# Bluetooth_Module_Programmer.net
KiCad netlist of a schematic drawn in Altium Designer
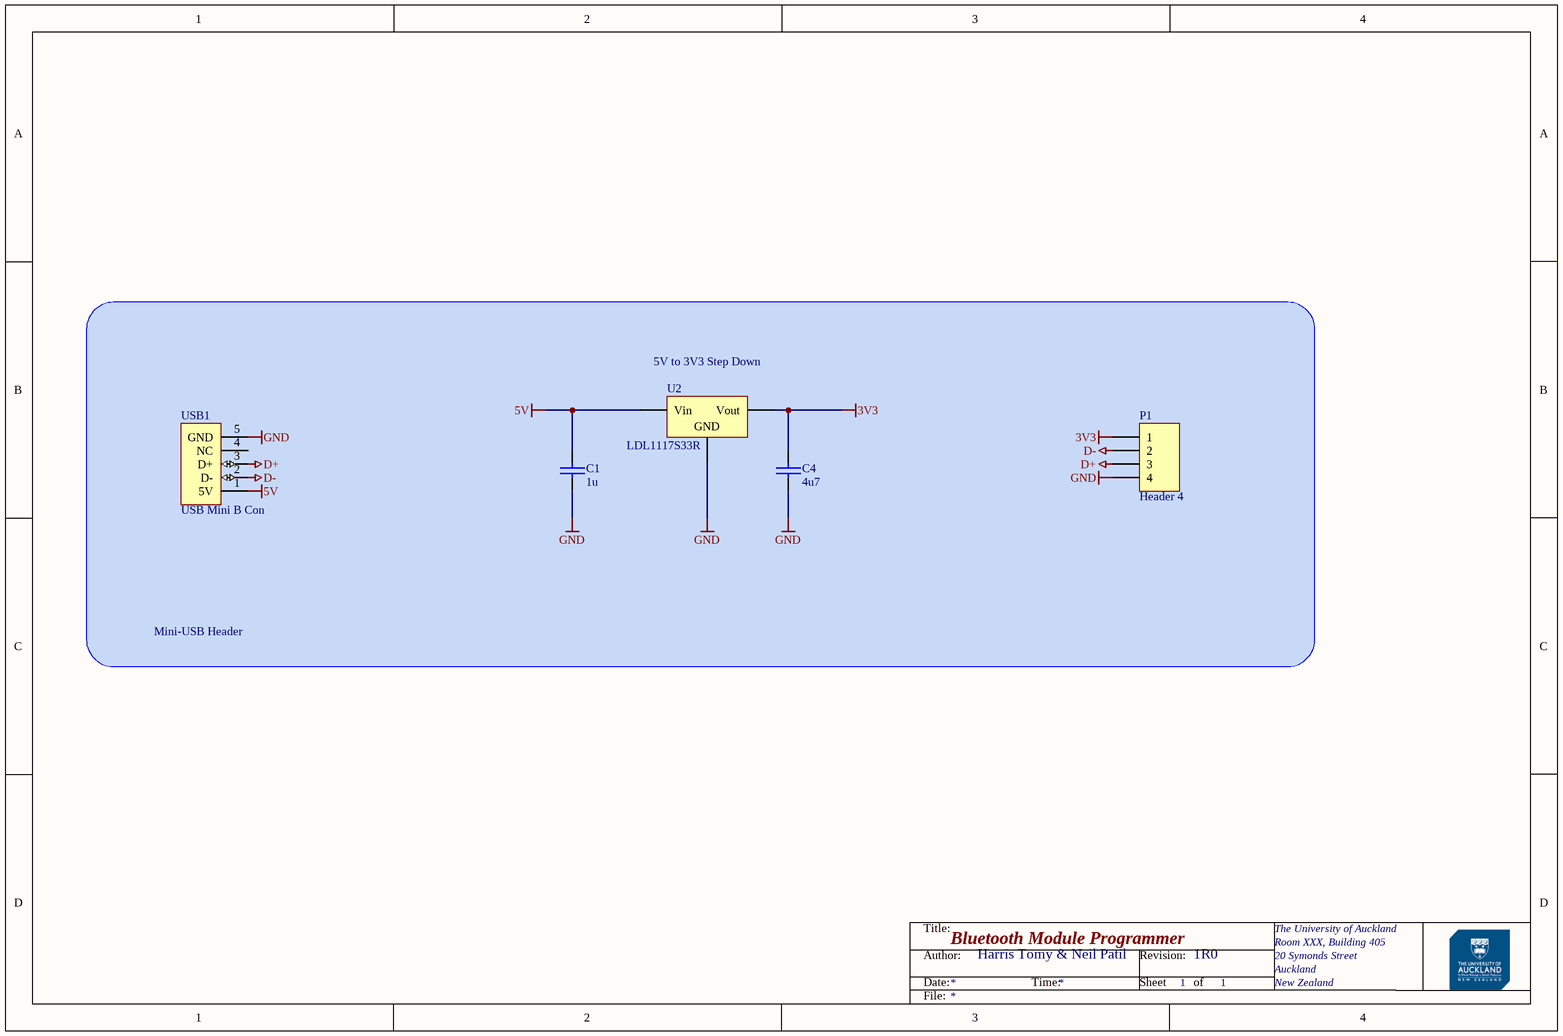
[diagram p0: Bluetooth_Module_Programmer.SchDoc]

(export (version "E")
  (design (tool "Eeschema 10.0.6"))
  (components
    (comp (ref "C1")
      (value "1u")
      (footprint "C1206")
      (description "CAP CER 0.1UF 100V C0G 1206")
      (fields (field (name "MPN") "C3216C0G2A104J160AC") (field (name "MANUFACTURER") "TDK Corporation"))
      (libsource (lib "E209_Lib") (part "Cap CER Decoup C3216C0G2A104J160AC"))
    )
    (comp (ref "C4")
      (value "4u7")
      (footprint "C1206")
      (description "CAP CER 0.1UF 100V C0G 1206")
      (fields (field (name "MPN") "C3216C0G2A104J160AC") (field (name "MANUFACTURER") "TDK Corporation"))
      (libsource (lib "E209_Lib") (part "Cap CER Decoup C3216C0G2A104J160AC"))
    )
    (comp (ref "P1")
      (value "Header 4")
      (footprint "HDR1X4")
      (description "Header, 4-Pin")
      (fields (field (name "PUBLISHER") "Altium Limited"))
      (libsource (lib "Miscellaneous Connectors") (part "Header 4"))
    )
    (comp (ref "U2")
      (value "LDL1117S33R")
      (footprint "SOT223L")
      (description "IC REG LINEAR 3.3V 1.2A SOT223")
      (fields (field (name "MANUFACTURER") "STMicroelectronics"))
      (libsource (lib "E209_Lib") (part "LDO LDL1117S33R"))
    )
    (comp (ref "USB1")
      (value "USB Mini B Con")
      (footprint "USB_UJ2MAB")
      (libsource (lib "CommonDevices_V1") (part "USBMiniB"))
    )
  )
  (nets
    (net (code "1") (name "3V3") (class "Default")
      (node (ref "C4") (pin "2") (pinfunction "2_2") (pintype "passive"))
      (node (ref "P1") (pin "1") (pinfunction "1_1") (pintype "passive"))
      (node (ref "U2") (pin "2") (pinfunction "Vout_2") (pintype "passive"))
    )
    (net (code "2") (name "5V") (class "Default")
      (node (ref "C1") (pin "2") (pinfunction "2_2") (pintype "passive"))
      (node (ref "U2") (pin "3") (pinfunction "Vin_3") (pintype "passive"))
      (node (ref "USB1") (pin "1") (pinfunction "5V_1") (pintype "passive"))
    )
    (net (code "3") (name "D+") (class "Default")
      (node (ref "P1") (pin "3") (pinfunction "3_3") (pintype "passive"))
      (node (ref "USB1") (pin "3") (pinfunction "D+_3") (pintype "bidirectional"))
    )
    (net (code "4") (name "D-") (class "Default")
      (node (ref "P1") (pin "2") (pinfunction "2_2") (pintype "passive"))
      (node (ref "USB1") (pin "2") (pinfunction "D-_2") (pintype "bidirectional"))
    )
    (net (code "5") (name "GND") (class "Default")
      (node (ref "C1") (pin "1") (pinfunction "1_1") (pintype "passive"))
      (node (ref "C4") (pin "1") (pinfunction "1_1") (pintype "passive"))
      (node (ref "P1") (pin "4") (pinfunction "4_4") (pintype "passive"))
      (node (ref "U2") (pin "1") (pinfunction "GND_1") (pintype "passive"))
      (node (ref "USB1") (pin "5") (pinfunction "GND_5") (pintype "passive"))
    )
    (net (code "6") (name "unconnected-(USB1-NC-Pad4)") (class "Default")
      (node (ref "USB1") (pin "4") (pinfunction "NC_4") (pintype "passive"))
    )
  )
)
